# MK.net
KiCad netlist of a schematic drawn in Altium Designer
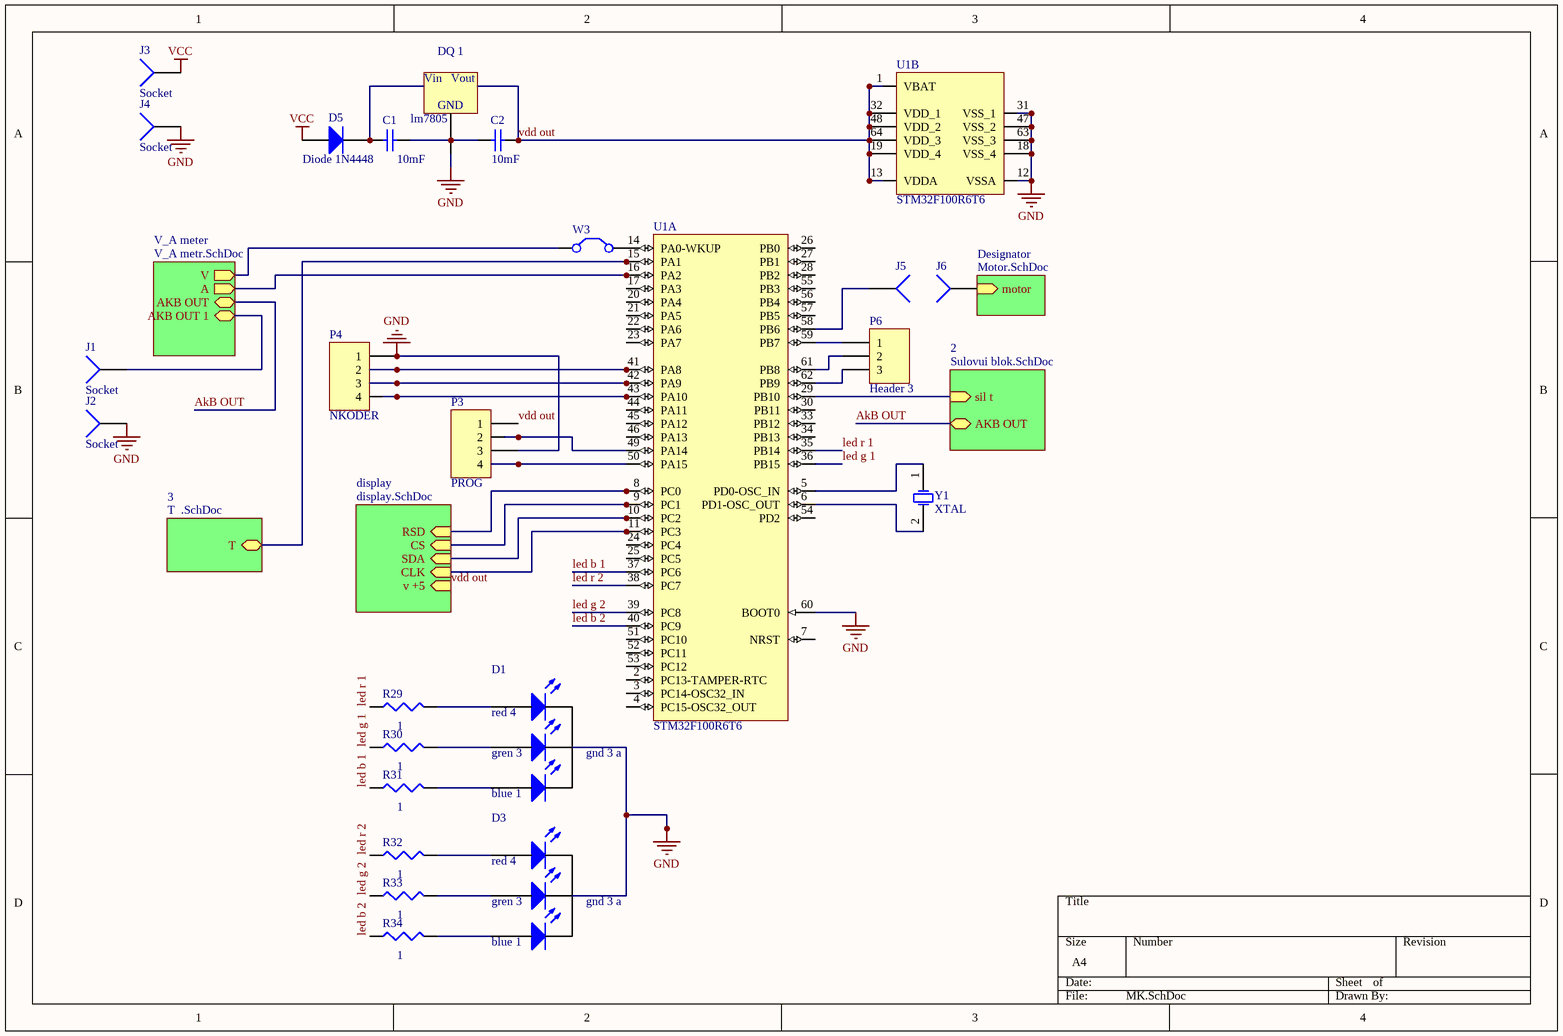
[diagram p0: MK.SchDoc]

(export (version "E")
  (design (tool "Eeschema 10.0.6"))
  (components
    (comp (ref "C1")
      (value "10mF")
      (footprint "C1206")
      (description "Capacitor (Semiconductor SIM Model)")
      (fields (field (name "Comment") "Cap Semi") (field (name "PUBLISHER") "Altium Limited"))
      (libsource (lib "Miscellaneous Devices") (part "Cap Semi"))
    )
    (comp (ref "C2")
      (value "10mF")
      (footprint "C1206")
      (description "Capacitor (Semiconductor SIM Model)")
      (fields (field (name "Comment") "Cap Semi") (field (name "PUBLISHER") "Altium Limited"))
      (libsource (lib "Miscellaneous Devices") (part "Cap Semi"))
    )
    (comp (ref "D1")
      (value "LED1")
      (footprint "led rgb:PCBComponent_1")
      (description "Typical RED GaAs LED")
      (fields (field (name "PUBLISHER") "Altium Limited"))
      (libsource (lib "led RGB") (part "LED1"))
    )
    (comp (ref "D3")
      (value "LED1")
      (footprint "led rgb:PCBComponent_1")
      (description "Typical RED GaAs LED")
      (fields (field (name "PUBLISHER") "Altium Limited"))
      (libsource (lib "led RGB") (part "LED1"))
    )
    (comp (ref "D5")
      (value "Diode 1N4448")
      (footprint "DO-35")
      (description "High Conductance Fast Diode")
      (fields (field (name "PUBLISHER") "Altium Limited"))
      (libsource (lib "Miscellaneous Devices") (part "Diode 1N4448"))
    )
    (comp (ref "DQ 1")
      (value "lm7805")
      (footprint "Miscellaneous Devices:TO-220AB")
      (libsource (lib "lm 7805") (part "lm7805"))
    )
    (comp (ref "J1")
      (value "Socket")
      (footprint "PIN1")
      (fields (field (name "PUBLISHER") "Altium Limited"))
      (libsource (lib "Miscellaneous Connectors") (part "Socket"))
    )
    (comp (ref "J2")
      (value "Socket")
      (footprint "PIN1")
      (fields (field (name "PUBLISHER") "Altium Limited"))
      (libsource (lib "Miscellaneous Connectors") (part "Socket"))
    )
    (comp (ref "J3")
      (value "Socket")
      (footprint "PIN1")
      (fields (field (name "PUBLISHER") "Altium Limited"))
      (libsource (lib "Miscellaneous Connectors") (part "Socket"))
    )
    (comp (ref "J4")
      (value "Socket")
      (footprint "PIN1")
      (fields (field (name "PUBLISHER") "Altium Limited"))
      (libsource (lib "Miscellaneous Connectors") (part "Socket"))
    )
    (comp (ref "J5")
      (value "Socket")
      (footprint "PIN1")
      (fields (field (name "PUBLISHER") "Altium Limited"))
      (libsource (lib "Miscellaneous Connectors") (part "Socket"))
    )
    (comp (ref "J6")
      (value "Socket")
      (footprint "PIN1")
      (fields (field (name "PUBLISHER") "Altium Limited"))
      (libsource (lib "Miscellaneous Connectors") (part "Socket"))
    )
    (comp (ref "P3")
      (value "PROG")
      (footprint "HDR1X4")
      (description "Header, 4-Pin")
      (fields (field (name "PUBLISHER") "Altium Limited"))
      (libsource (lib "Miscellaneous Connectors") (part "Header 4"))
    )
    (comp (ref "P4")
      (value "NKODER")
      (footprint "HDR1X4")
      (description "Header, 4-Pin")
      (fields (field (name "PUBLISHER") "Altium Limited"))
      (libsource (lib "Miscellaneous Connectors") (part "Header 4"))
    )
    (comp (ref "P6")
      (value "Header 3")
      (footprint "HDR1X3")
      (description "Header, 3-Pin")
      (fields (field (name "PUBLISHER") "Altium Limited"))
      (libsource (lib "Miscellaneous Connectors") (part "Header 3"))
    )
    (comp (ref "R29")
      (value "1")
      (footprint "J1-0603")
      (description "Resistor")
      (fields (field (name "Comment") "Res3") (field (name "PUBLISHER") "Altium Limited"))
      (libsource (lib "Miscellaneous Devices") (part "Res3"))
    )
    (comp (ref "R30")
      (value "1")
      (footprint "J1-0603")
      (description "Resistor")
      (fields (field (name "Comment") "Res3") (field (name "PUBLISHER") "Altium Limited"))
      (libsource (lib "Miscellaneous Devices") (part "Res3"))
    )
    (comp (ref "R31")
      (value "1")
      (footprint "J1-0603")
      (description "Resistor")
      (fields (field (name "Comment") "Res3") (field (name "PUBLISHER") "Altium Limited"))
      (libsource (lib "Miscellaneous Devices") (part "Res3"))
    )
    (comp (ref "R32")
      (value "1")
      (footprint "J1-0603")
      (description "Resistor")
      (fields (field (name "Comment") "Res3") (field (name "PUBLISHER") "Altium Limited"))
      (libsource (lib "Miscellaneous Devices") (part "Res3"))
    )
    (comp (ref "R33")
      (value "1")
      (footprint "J1-0603")
      (description "Resistor")
      (fields (field (name "Comment") "Res3") (field (name "PUBLISHER") "Altium Limited"))
      (libsource (lib "Miscellaneous Devices") (part "Res3"))
    )
    (comp (ref "R34")
      (value "1")
      (footprint "J1-0603")
      (description "Resistor")
      (fields (field (name "Comment") "Res3") (field (name "PUBLISHER") "Altium Limited"))
      (libsource (lib "Miscellaneous Devices") (part "Res3"))
    )
    (comp (ref "U1")
      (value "STM32F100R6T6")
      (footprint "STM-LQFP64_N")
      (libsource (lib "STMicroelectronics STM32 F1") (part "STM32F100R6T6"))
    )
    (comp (ref "W3")
      (value "Jumper")
      (footprint "JAMP:PCBComponent_1")
      (description "Jumper Wire")
      (fields (field (name "PUBLISHER") "Altium Limited"))
      (libsource (lib "JAMP") (part "Jumper"))
    )
    (comp (ref "Y1")
      (value "XTAL")
      (footprint "X talk rez1:PCBComponent_1")
      (description "Crystal Oscillator")
      (fields (field (name "PUBLISHER") "Altium Limited"))
      (libsource (lib "X talk 1") (part "XTAL"))
    )
  )
  (nets
    (net (code "1") (name "/A") (class "Default")
      (node (ref "U1") (pin "16") (pinfunction "PA2_16") (pintype "bidirectional"))
    )
    (net (code "2") (name "/AKB OUT 1") (class "Default")
      (node (ref "J1") (pin "1") (pinfunction "1_1") (pintype "passive"))
    )
    (net (code "4") (name "/CLK") (class "Default")
      (node (ref "U1") (pin "11") (pinfunction "PC3_11") (pintype "bidirectional"))
    )
    (net (code "5") (name "/CS") (class "Default")
      (node (ref "U1") (pin "9") (pinfunction "PC1_9") (pintype "bidirectional"))
    )
    (net (code "6") (name "/RSD") (class "Default")
      (node (ref "U1") (pin "8") (pinfunction "PC0_8") (pintype "bidirectional"))
    )
    (net (code "7") (name "/SDA") (class "Default")
      (node (ref "U1") (pin "10") (pinfunction "PC2_10") (pintype "bidirectional"))
    )
    (net (code "8") (name "/T") (class "Default")
      (node (ref "U1") (pin "15") (pinfunction "PA1_15") (pintype "bidirectional"))
    )
    (net (code "9") (name "/V") (class "Default")
      (node (ref "W3") (pin "1") (pinfunction "C1_1") (pintype "passive"))
    )
    (net (code "10") (name "/led b 1") (class "Default")
      (node (ref "R31") (pin "1") (pinfunction "1_1") (pintype "passive"))
      (node (ref "U1") (pin "37") (pinfunction "PC6_37") (pintype "bidirectional"))
    )
    (net (code "11") (name "/led b 2") (class "Default")
      (node (ref "R34") (pin "1") (pinfunction "1_1") (pintype "passive"))
      (node (ref "U1") (pin "40") (pinfunction "PC9_40") (pintype "bidirectional"))
    )
    (net (code "12") (name "/led g 1") (class "Default")
      (node (ref "R30") (pin "1") (pinfunction "1_1") (pintype "passive"))
      (node (ref "U1") (pin "36") (pinfunction "PB15_36") (pintype "bidirectional"))
    )
    (net (code "13") (name "/led g 2") (class "Default")
      (node (ref "R33") (pin "1") (pinfunction "1_1") (pintype "passive"))
      (node (ref "U1") (pin "39") (pinfunction "PC8_39") (pintype "bidirectional"))
    )
    (net (code "14") (name "/led r 1") (class "Default")
      (node (ref "R29") (pin "1") (pinfunction "1_1") (pintype "passive"))
      (node (ref "U1") (pin "35") (pinfunction "PB14_35") (pintype "bidirectional"))
    )
    (net (code "15") (name "/led r 2") (class "Default")
      (node (ref "R32") (pin "1") (pinfunction "1_1") (pintype "passive"))
      (node (ref "U1") (pin "38") (pinfunction "PC7_38") (pintype "bidirectional"))
    )
    (net (code "16") (name "/motor") (class "Default")
      (node (ref "J6") (pin "1") (pinfunction "1_1") (pintype "passive"))
    )
    (net (code "17") (name "/sil t") (class "Default")
      (node (ref "U1") (pin "29") (pinfunction "PB10_29") (pintype "bidirectional"))
    )
    (net (code "18") (name "/vdd out") (class "Default")
      (node (ref "C2") (pin "2") (pinfunction "2_2") (pintype "passive"))
      (node (ref "DQ 1") (pin "3") (pinfunction "Vuot_3") (pintype "passive"))
      (node (ref "P3") (pin "1") (pinfunction "1_1") (pintype "passive"))
      (node (ref "U1") (pin "1") (pinfunction "VBAT_1") (pintype "power_in"))
      (node (ref "U1") (pin "13") (pinfunction "VDDA_13") (pintype "power_in"))
      (node (ref "U1") (pin "19") (pinfunction "VDD_4_19") (pintype "power_in"))
      (node (ref "U1") (pin "32") (pinfunction "VDD_1_32") (pintype "power_in"))
      (node (ref "U1") (pin "48") (pinfunction "VDD_2_48") (pintype "power_in"))
      (node (ref "U1") (pin "64") (pinfunction "VDD_3_64") (pintype "power_in"))
    )
    (net (code "19") (name "GND") (class "Default")
      (node (ref "C1") (pin "2") (pinfunction "2_2") (pintype "passive"))
      (node (ref "C2") (pin "1") (pinfunction "1_1") (pintype "passive"))
      (node (ref "D1") (pin "2") (pinfunction "gnd_2") (pintype "passive"))
      (node (ref "D3") (pin "2") (pinfunction "gnd_2") (pintype "passive"))
      (node (ref "DQ 1") (pin "2") (pinfunction "GND_2") (pintype "passive"))
      (node (ref "J2") (pin "1") (pinfunction "1_1") (pintype "passive"))
      (node (ref "J4") (pin "1") (pinfunction "1_1") (pintype "passive"))
      (node (ref "P3") (pin "3") (pinfunction "3_3") (pintype "passive"))
      (node (ref "P4") (pin "1") (pinfunction "1_1") (pintype "passive"))
      (node (ref "U1") (pin "12") (pinfunction "VSSA_12") (pintype "power_in"))
      (node (ref "U1") (pin "18") (pinfunction "VSS_4_18") (pintype "power_in"))
      (node (ref "U1") (pin "31") (pinfunction "VSS_1_31") (pintype "power_in"))
      (node (ref "U1") (pin "47") (pinfunction "VSS_2_47") (pintype "power_in"))
      (node (ref "U1") (pin "60") (pinfunction "BOOT0_60") (pintype "input"))
      (node (ref "U1") (pin "63") (pinfunction "VSS_3_63") (pintype "power_in"))
    )
    (net (code "20") (name "Net-(D1-blue)") (class "Default")
      (node (ref "D1") (pin "1") (pinfunction "blue_1") (pintype "passive"))
      (node (ref "R31") (pin "2") (pinfunction "2_2") (pintype "passive"))
    )
    (net (code "21") (name "Net-(D1-gren)") (class "Default")
      (node (ref "D1") (pin "3") (pinfunction "gren_3") (pintype "passive"))
      (node (ref "R30") (pin "2") (pinfunction "2_2") (pintype "passive"))
    )
    (net (code "22") (name "Net-(D1-red_k)") (class "Default")
      (node (ref "D1") (pin "4") (pinfunction "red_k_4") (pintype "passive"))
      (node (ref "R29") (pin "2") (pinfunction "2_2") (pintype "passive"))
    )
    (net (code "23") (name "Net-(D3-blue)") (class "Default")
      (node (ref "D3") (pin "1") (pinfunction "blue_1") (pintype "passive"))
      (node (ref "R34") (pin "2") (pinfunction "2_2") (pintype "passive"))
    )
    (net (code "24") (name "Net-(D3-gren)") (class "Default")
      (node (ref "D3") (pin "3") (pinfunction "gren_3") (pintype "passive"))
      (node (ref "R33") (pin "2") (pinfunction "2_2") (pintype "passive"))
    )
    (net (code "25") (name "Net-(D3-red_k)") (class "Default")
      (node (ref "D3") (pin "4") (pinfunction "red_k_4") (pintype "passive"))
      (node (ref "R32") (pin "2") (pinfunction "2_2") (pintype "passive"))
    )
    (net (code "26") (name "Net-(D5-K)") (class "Default")
      (node (ref "C1") (pin "1") (pinfunction "1_1") (pintype "passive"))
      (node (ref "D5") (pin "2") (pinfunction "K_2") (pintype "passive"))
      (node (ref "DQ 1") (pin "1") (pinfunction "Vin_1") (pintype "passive"))
    )
    (net (code "27") (name "Net-(U1A-PA0-WKUP)") (class "Default")
      (node (ref "U1") (pin "14") (pinfunction "PA0-WKUP_14") (pintype "bidirectional"))
      (node (ref "W3") (pin "2") (pinfunction "C2_2") (pintype "passive"))
    )
    (net (code "28") (name "Net-(U1A-PA8)") (class "Default")
      (node (ref "P4") (pin "2") (pinfunction "2_2") (pintype "passive"))
      (node (ref "U1") (pin "41") (pinfunction "PA8_41") (pintype "bidirectional"))
    )
    (net (code "29") (name "Net-(U1A-PA9)") (class "Default")
      (node (ref "P4") (pin "3") (pinfunction "3_3") (pintype "passive"))
      (node (ref "U1") (pin "42") (pinfunction "PA9_42") (pintype "bidirectional"))
    )
    (net (code "30") (name "Net-(U1A-PA10)") (class "Default")
      (node (ref "P4") (pin "4") (pinfunction "4_4") (pintype "passive"))
      (node (ref "U1") (pin "43") (pinfunction "PA10_43") (pintype "bidirectional"))
    )
    (net (code "31") (name "Net-(U1A-PA14)") (class "Default")
      (node (ref "P3") (pin "2") (pinfunction "2_2") (pintype "passive"))
      (node (ref "U1") (pin "49") (pinfunction "PA14_49") (pintype "bidirectional"))
    )
    (net (code "32") (name "Net-(U1A-PA15)") (class "Default")
      (node (ref "P3") (pin "4") (pinfunction "4_4") (pintype "passive"))
      (node (ref "U1") (pin "50") (pinfunction "PA15_50") (pintype "bidirectional"))
    )
    (net (code "33") (name "Net-(U1A-PB6)") (class "Default")
      (node (ref "J5") (pin "1") (pinfunction "1_1") (pintype "passive"))
      (node (ref "U1") (pin "58") (pinfunction "PB6_58") (pintype "bidirectional"))
    )
    (net (code "34") (name "Net-(U1A-PB7)") (class "Default")
      (node (ref "P6") (pin "1") (pinfunction "1_1") (pintype "passive"))
      (node (ref "U1") (pin "59") (pinfunction "PB7_59") (pintype "bidirectional"))
    )
    (net (code "35") (name "Net-(U1A-PB8)") (class "Default")
      (node (ref "P6") (pin "2") (pinfunction "2_2") (pintype "passive"))
      (node (ref "U1") (pin "61") (pinfunction "PB8_61") (pintype "bidirectional"))
    )
    (net (code "36") (name "Net-(U1A-PB9)") (class "Default")
      (node (ref "P6") (pin "3") (pinfunction "3_3") (pintype "passive"))
      (node (ref "U1") (pin "62") (pinfunction "PB9_62") (pintype "bidirectional"))
    )
    (net (code "37") (name "Net-(U1A-PD0-OSC_IN)") (class "Default")
      (node (ref "U1") (pin "5") (pinfunction "PD0-OSC_IN_5") (pintype "bidirectional"))
      (node (ref "Y1") (pin "1") (pinfunction "OSC1_1") (pintype "passive"))
    )
    (net (code "38") (name "Net-(U1A-PD1-OSC_OUT)") (class "Default")
      (node (ref "U1") (pin "6") (pinfunction "PD1-OSC_OUT_6") (pintype "bidirectional"))
      (node (ref "Y1") (pin "2") (pinfunction "OSC2_2") (pintype "passive"))
    )
    (net (code "39") (name "VCC") (class "Default")
      (node (ref "D5") (pin "1") (pinfunction "A_1") (pintype "passive"))
      (node (ref "J3") (pin "1") (pinfunction "1_1") (pintype "passive"))
    )
    (net (code "40") (name "unconnected-(U1A-NRST-Pad7)") (class "Default")
      (node (ref "U1") (pin "7") (pinfunction "NRST_7") (pintype "bidirectional"))
    )
    (net (code "41") (name "unconnected-(U1A-PA3-Pad17)") (class "Default")
      (node (ref "U1") (pin "17") (pinfunction "PA3_17") (pintype "bidirectional"))
    )
    (net (code "42") (name "unconnected-(U1A-PA4-Pad20)") (class "Default")
      (node (ref "U1") (pin "20") (pinfunction "PA4_20") (pintype "bidirectional"))
    )
    (net (code "43") (name "unconnected-(U1A-PA5-Pad21)") (class "Default")
      (node (ref "U1") (pin "21") (pinfunction "PA5_21") (pintype "bidirectional"))
    )
    (net (code "44") (name "unconnected-(U1A-PA6-Pad22)") (class "Default")
      (node (ref "U1") (pin "22") (pinfunction "PA6_22") (pintype "bidirectional"))
    )
    (net (code "45") (name "unconnected-(U1A-PA7-Pad23)") (class "Default")
      (node (ref "U1") (pin "23") (pinfunction "PA7_23") (pintype "bidirectional"))
    )
    (net (code "46") (name "unconnected-(U1A-PA11-Pad44)") (class "Default")
      (node (ref "U1") (pin "44") (pinfunction "PA11_44") (pintype "bidirectional"))
    )
    (net (code "47") (name "unconnected-(U1A-PA12-Pad45)") (class "Default")
      (node (ref "U1") (pin "45") (pinfunction "PA12_45") (pintype "bidirectional"))
    )
    (net (code "48") (name "unconnected-(U1A-PA13-Pad46)") (class "Default")
      (node (ref "U1") (pin "46") (pinfunction "PA13_46") (pintype "bidirectional"))
    )
    (net (code "49") (name "unconnected-(U1A-PB0-Pad26)") (class "Default")
      (node (ref "U1") (pin "26") (pinfunction "PB0_26") (pintype "bidirectional"))
    )
    (net (code "50") (name "unconnected-(U1A-PB1-Pad27)") (class "Default")
      (node (ref "U1") (pin "27") (pinfunction "PB1_27") (pintype "bidirectional"))
    )
    (net (code "51") (name "unconnected-(U1A-PB2-Pad28)") (class "Default")
      (node (ref "U1") (pin "28") (pinfunction "PB2_28") (pintype "bidirectional"))
    )
    (net (code "52") (name "unconnected-(U1A-PB3-Pad55)") (class "Default")
      (node (ref "U1") (pin "55") (pinfunction "PB3_55") (pintype "bidirectional"))
    )
    (net (code "53") (name "unconnected-(U1A-PB4-Pad56)") (class "Default")
      (node (ref "U1") (pin "56") (pinfunction "PB4_56") (pintype "bidirectional"))
    )
    (net (code "54") (name "unconnected-(U1A-PB5-Pad57)") (class "Default")
      (node (ref "U1") (pin "57") (pinfunction "PB5_57") (pintype "bidirectional"))
    )
    (net (code "55") (name "unconnected-(U1A-PB11-Pad30)") (class "Default")
      (node (ref "U1") (pin "30") (pinfunction "PB11_30") (pintype "bidirectional"))
    )
    (net (code "56") (name "unconnected-(U1A-PB12-Pad33)") (class "Default")
      (node (ref "U1") (pin "33") (pinfunction "PB12_33") (pintype "bidirectional"))
    )
    (net (code "57") (name "unconnected-(U1A-PB13-Pad34)") (class "Default")
      (node (ref "U1") (pin "34") (pinfunction "PB13_34") (pintype "bidirectional"))
    )
    (net (code "58") (name "unconnected-(U1A-PC4-Pad24)") (class "Default")
      (node (ref "U1") (pin "24") (pinfunction "PC4_24") (pintype "bidirectional"))
    )
    (net (code "59") (name "unconnected-(U1A-PC5-Pad25)") (class "Default")
      (node (ref "U1") (pin "25") (pinfunction "PC5_25") (pintype "bidirectional"))
    )
    (net (code "60") (name "unconnected-(U1A-PC10-Pad51)") (class "Default")
      (node (ref "U1") (pin "51") (pinfunction "PC10_51") (pintype "bidirectional"))
    )
    (net (code "61") (name "unconnected-(U1A-PC11-Pad52)") (class "Default")
      (node (ref "U1") (pin "52") (pinfunction "PC11_52") (pintype "bidirectional"))
    )
    (net (code "62") (name "unconnected-(U1A-PC12-Pad53)") (class "Default")
      (node (ref "U1") (pin "53") (pinfunction "PC12_53") (pintype "bidirectional"))
    )
    (net (code "63") (name "unconnected-(U1A-PC13-TAMPER-RTC-Pad2)") (class "Default")
      (node (ref "U1") (pin "2") (pinfunction "PC13-TAMPER-RTC_2") (pintype "bidirectional"))
    )
    (net (code "64") (name "unconnected-(U1A-PC14-OSC32_IN-Pad3)") (class "Default")
      (node (ref "U1") (pin "3") (pinfunction "PC14-OSC32_IN_3") (pintype "bidirectional"))
    )
    (net (code "65") (name "unconnected-(U1A-PC15-OSC32_OUT-Pad4)") (class "Default")
      (node (ref "U1") (pin "4") (pinfunction "PC15-OSC32_OUT_4") (pintype "bidirectional"))
    )
    (net (code "66") (name "unconnected-(U1A-PD2-Pad54)") (class "Default")
      (node (ref "U1") (pin "54") (pinfunction "PD2_54") (pintype "bidirectional"))
    )
  )
)
